# Control.net
KiCad netlist of a schematic drawn in Altium Designer
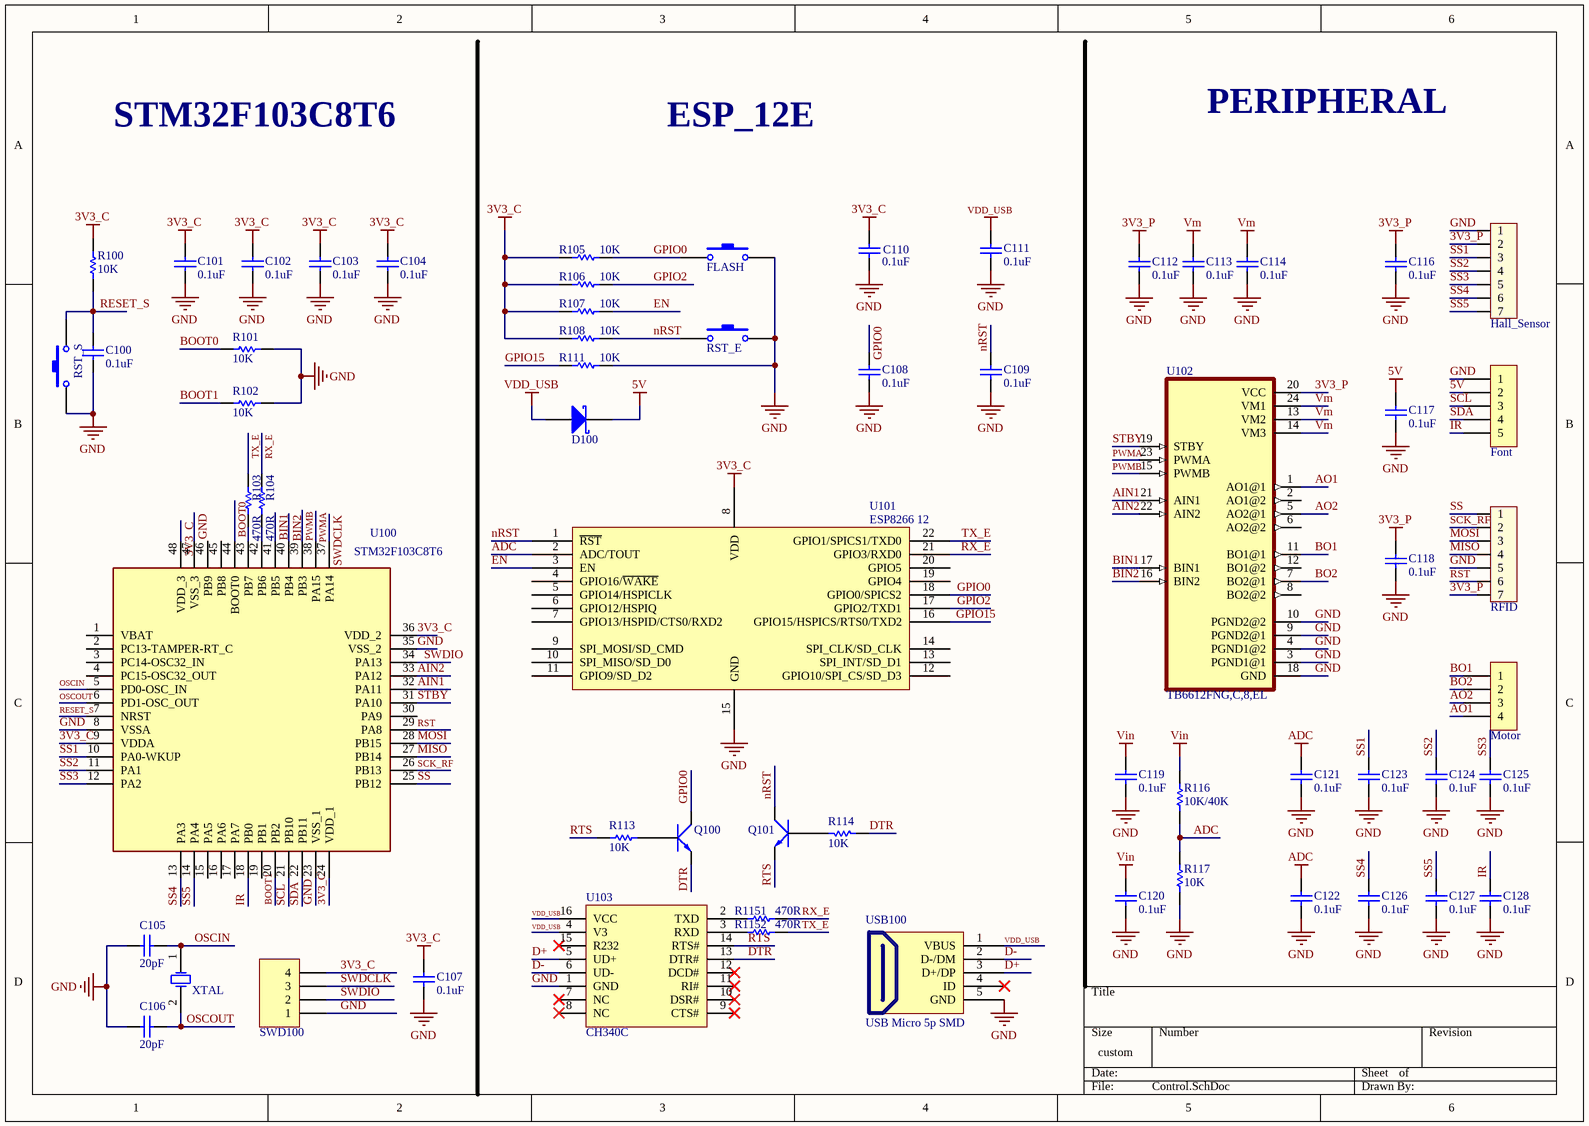
[diagram p0: Control.SchDoc]

(export (version "E")
  (design (tool "Eeschema 10.0.6"))
  (components
    (comp (ref "C100")
      (value "0.1uF")
      (footprint "CAP-SM-0805")
      (description "Capacitor")
      (fields (field (name "Comment") "Cap Non-Pol SMD"))
      (libsource (lib "PIF_Library") (part "Cap Non-Pol SMD"))
    )
    (comp (ref "C101")
      (value "0.1uF")
      (footprint "CAP-SM-0805")
      (description "Capacitor")
      (fields (field (name "Comment") "Cap Non-Pol SMD"))
      (libsource (lib "PIF_Library") (part "Cap Non-Pol SMD"))
    )
    (comp (ref "C102")
      (value "0.1uF")
      (footprint "CAP-SM-0805")
      (description "Capacitor")
      (fields (field (name "Comment") "Cap Non-Pol SMD"))
      (libsource (lib "PIF_Library") (part "Cap Non-Pol SMD"))
    )
    (comp (ref "C103")
      (value "0.1uF")
      (footprint "CAP-SM-0805")
      (description "Capacitor")
      (fields (field (name "Comment") "Cap Non-Pol SMD"))
      (libsource (lib "PIF_Library") (part "Cap Non-Pol SMD"))
    )
    (comp (ref "C104")
      (value "0.1uF")
      (footprint "CAP-SM-0805")
      (description "Capacitor")
      (fields (field (name "Comment") "Cap Non-Pol SMD"))
      (libsource (lib "PIF_Library") (part "Cap Non-Pol SMD"))
    )
    (comp (ref "C105")
      (value "20pF")
      (footprint "CAP-SM-0805")
      (description "Capacitor")
      (fields (field (name "Comment") "Cap Non-Pol SMD"))
      (libsource (lib "PIF_Library") (part "Cap Non-Pol SMD"))
    )
    (comp (ref "C106")
      (value "20pF")
      (footprint "CAP-SM-0805")
      (description "Capacitor")
      (fields (field (name "Comment") "Cap Non-Pol SMD"))
      (libsource (lib "PIF_Library") (part "Cap Non-Pol SMD"))
    )
    (comp (ref "C107")
      (value "0.1uF")
      (footprint "CAP-SM-0805")
      (description "Capacitor")
      (fields (field (name "Comment") "Cap Non-Pol SMD"))
      (libsource (lib "PIF_Library") (part "Cap Non-Pol SMD"))
    )
    (comp (ref "C108")
      (value "0.1uF")
      (footprint "CAP-SM-0805")
      (description "Capacitor")
      (fields (field (name "Comment") "Cap Non-Pol SMD"))
      (libsource (lib "PIF_Library") (part "Cap Non-Pol SMD"))
    )
    (comp (ref "C109")
      (value "0.1uF")
      (footprint "CAP-SM-0805")
      (description "Capacitor")
      (fields (field (name "Comment") "Cap Non-Pol SMD"))
      (libsource (lib "PIF_Library") (part "Cap Non-Pol SMD"))
    )
    (comp (ref "C110")
      (value "0.1uF")
      (footprint "CAP-SM-0805")
      (description "Capacitor")
      (fields (field (name "Comment") "Cap Non-Pol SMD"))
      (libsource (lib "PIF_Library") (part "Cap Non-Pol SMD"))
    )
    (comp (ref "C111")
      (value "0.1uF")
      (footprint "CAP-SM-0805")
      (description "Capacitor")
      (fields (field (name "Comment") "Cap Non-Pol SMD"))
      (libsource (lib "PIF_Library") (part "Cap Non-Pol SMD"))
    )
    (comp (ref "C112")
      (value "0.1uF")
      (footprint "CAP-SM-0805")
      (description "Capacitor")
      (fields (field (name "Comment") "Cap Non-Pol SMD"))
      (libsource (lib "PIF_Library") (part "Cap Non-Pol SMD"))
    )
    (comp (ref "C113")
      (value "0.1uF")
      (footprint "CAP-SM-0805")
      (description "Capacitor")
      (fields (field (name "Comment") "Cap Non-Pol SMD"))
      (libsource (lib "PIF_Library") (part "Cap Non-Pol SMD"))
    )
    (comp (ref "C114")
      (value "0.1uF")
      (footprint "CAP-SM-0805")
      (description "Capacitor")
      (fields (field (name "Comment") "Cap Non-Pol SMD"))
      (libsource (lib "PIF_Library") (part "Cap Non-Pol SMD"))
    )
    (comp (ref "C116")
      (value "0.1uF")
      (footprint "CAP-SM-0805")
      (description "Capacitor")
      (fields (field (name "Comment") "Cap Non-Pol SMD"))
      (libsource (lib "PIF_Library") (part "Cap Non-Pol SMD"))
    )
    (comp (ref "C117")
      (value "0.1uF")
      (footprint "CAP-SM-0805")
      (description "Capacitor")
      (fields (field (name "Comment") "Cap Non-Pol SMD"))
      (libsource (lib "PIF_Library") (part "Cap Non-Pol SMD"))
    )
    (comp (ref "C118")
      (value "0.1uF")
      (footprint "CAP-SM-0805")
      (description "Capacitor")
      (fields (field (name "Comment") "Cap Non-Pol SMD"))
      (libsource (lib "PIF_Library") (part "Cap Non-Pol SMD"))
    )
    (comp (ref "C119")
      (value "0.1uF")
      (footprint "CAP-SM-0805")
      (description "Capacitor")
      (fields (field (name "Comment") "Cap Non-Pol SMD"))
      (libsource (lib "PIF_Library") (part "Cap Non-Pol SMD"))
    )
    (comp (ref "C120")
      (value "0.1uF")
      (footprint "CAP-SM-0805")
      (description "Capacitor")
      (fields (field (name "Comment") "Cap Non-Pol SMD"))
      (libsource (lib "PIF_Library") (part "Cap Non-Pol SMD"))
    )
    (comp (ref "C121")
      (value "0.1uF")
      (footprint "CAP-SM-0805")
      (description "Capacitor")
      (fields (field (name "Comment") "Cap Non-Pol SMD"))
      (libsource (lib "PIF_Library") (part "Cap Non-Pol SMD"))
    )
    (comp (ref "C122")
      (value "0.1uF")
      (footprint "CAP-SM-0805")
      (description "Capacitor")
      (fields (field (name "Comment") "Cap Non-Pol SMD"))
      (libsource (lib "PIF_Library") (part "Cap Non-Pol SMD"))
    )
    (comp (ref "C123")
      (value "0.1uF")
      (footprint "CAP-SM-0805")
      (description "Capacitor")
      (fields (field (name "Comment") "Cap Non-Pol SMD"))
      (libsource (lib "PIF_Library") (part "Cap Non-Pol SMD"))
    )
    (comp (ref "C124")
      (value "0.1uF")
      (footprint "CAP-SM-0805")
      (description "Capacitor")
      (fields (field (name "Comment") "Cap Non-Pol SMD"))
      (libsource (lib "PIF_Library") (part "Cap Non-Pol SMD"))
    )
    (comp (ref "C125")
      (value "0.1uF")
      (footprint "CAP-SM-0805")
      (description "Capacitor")
      (fields (field (name "Comment") "Cap Non-Pol SMD"))
      (libsource (lib "PIF_Library") (part "Cap Non-Pol SMD"))
    )
    (comp (ref "C126")
      (value "0.1uF")
      (footprint "CAP-SM-0805")
      (description "Capacitor")
      (fields (field (name "Comment") "Cap Non-Pol SMD"))
      (libsource (lib "PIF_Library") (part "Cap Non-Pol SMD"))
    )
    (comp (ref "C127")
      (value "0.1uF")
      (footprint "CAP-SM-0805")
      (description "Capacitor")
      (fields (field (name "Comment") "Cap Non-Pol SMD"))
      (libsource (lib "PIF_Library") (part "Cap Non-Pol SMD"))
    )
    (comp (ref "C128")
      (value "0.1uF")
      (footprint "CAP-SM-0805")
      (description "Capacitor")
      (fields (field (name "Comment") "Cap Non-Pol SMD"))
      (libsource (lib "PIF_Library") (part "Cap Non-Pol SMD"))
    )
    (comp (ref "D100")
      (value "D Schottky")
      (footprint "SS34")
      (description "Schottky Diode")
      (fields (field (name "PUBLISHER") "Altium Limited"))
      (libsource (lib "PIF_Library") (part "D Schottky"))
    )
    (comp (ref "FLASH")
      (value "Tact SW - 2Pin")
      (footprint "SW-SMD")
      (description "Switch button 2 pin")
      (libsource (lib "PIF_Library") (part "Tact SW - 2Pin"))
    )
    (comp (ref "H100")
      (value "Hall_Sensor")
      (footprint "Header 7P DC 2.54")
      (description "Cắm")
      (libsource (lib "Altium_Lib_by_KhueNguyenCreator") (part "Header 7P 2.54 Duc Cong"))
    )
    (comp (ref "H101")
      (value "Font")
      (footprint "Header 5P DC 2.54")
      (description "Cắm")
      (libsource (lib "Altium_Lib_by_KhueNguyenCreator") (part "Header 5P 2.54 Duc Cong"))
    )
    (comp (ref "H102")
      (value "RFID")
      (footprint "Header 7P DC 2.54")
      (description "Cắm")
      (libsource (lib "Altium_Lib_by_KhueNguyenCreator") (part "Header 7P 2.54 Duc Cong"))
    )
    (comp (ref "H103")
      (value "Motor")
      (footprint "JP 1x4 DT")
      (description "Cắm")
      (libsource (lib "Altium_Lib_by_KhueNguyenCreator") (part "Header 4P 2.54 Duc Cong"))
    )
    (comp (ref "Q100")
      (value "HF")
      (footprint "SOT23")
      (description "NPN transistor")
      (libsource (lib "Altium_Lib_by_KhueNguyenCreator") (part "C1815 HF SMD"))
    )
    (comp (ref "Q101")
      (value "HF")
      (footprint "SOT23")
      (description "NPN transistor")
      (libsource (lib "Altium_Lib_by_KhueNguyenCreator") (part "C1815 HF SMD"))
    )
    (comp (ref "R100")
      (value "10K")
      (footprint "RES-SM-0805")
      (description "Resistor")
      (fields (field (name "Comment") "RESISTOR SMD"))
      (libsource (lib "PIF_Library") (part "RESISTOR SMD"))
    )
    (comp (ref "R101")
      (value "10K")
      (footprint "RES-SM-0805")
      (description "Resistor")
      (fields (field (name "Comment") "RESISTOR SMD"))
      (libsource (lib "PIF_Library") (part "RESISTOR SMD"))
    )
    (comp (ref "R102")
      (value "10K")
      (footprint "RES-SM-0805")
      (description "Resistor")
      (fields (field (name "Comment") "RESISTOR SMD"))
      (libsource (lib "PIF_Library") (part "RESISTOR SMD"))
    )
    (comp (ref "R103")
      (value "470R")
      (footprint "RES-SM-0805")
      (description "Resistor")
      (fields (field (name "Comment") "RESISTOR SMD"))
      (libsource (lib "PIF_Library") (part "RESISTOR SMD"))
    )
    (comp (ref "R104")
      (value "470R")
      (footprint "RES-SM-0805")
      (description "Resistor")
      (fields (field (name "Comment") "RESISTOR SMD"))
      (libsource (lib "PIF_Library") (part "RESISTOR SMD"))
    )
    (comp (ref "R105")
      (value "10K")
      (footprint "RES-SM-0805")
      (description "Resistor")
      (fields (field (name "Comment") "RESISTOR SMD"))
      (libsource (lib "PIF_Library") (part "RESISTOR SMD"))
    )
    (comp (ref "R106")
      (value "10K")
      (footprint "RES-SM-0805")
      (description "Resistor")
      (fields (field (name "Comment") "RESISTOR SMD"))
      (libsource (lib "PIF_Library") (part "RESISTOR SMD"))
    )
    (comp (ref "R107")
      (value "10K")
      (footprint "RES-SM-0805")
      (description "Resistor")
      (fields (field (name "Comment") "RESISTOR SMD"))
      (libsource (lib "PIF_Library") (part "RESISTOR SMD"))
    )
    (comp (ref "R108")
      (value "10K")
      (footprint "RES-SM-0805")
      (description "Resistor")
      (fields (field (name "Comment") "RESISTOR SMD"))
      (libsource (lib "PIF_Library") (part "RESISTOR SMD"))
    )
    (comp (ref "R111")
      (value "10K")
      (footprint "RES-SM-0805")
      (description "Resistor")
      (fields (field (name "Comment") "RESISTOR SMD"))
      (libsource (lib "PIF_Library") (part "RESISTOR SMD"))
    )
    (comp (ref "R113")
      (value "10K")
      (footprint "RES-SM-0805")
      (description "Resistor")
      (fields (field (name "Comment") "RESISTOR SMD"))
      (libsource (lib "PIF_Library") (part "RESISTOR SMD"))
    )
    (comp (ref "R114")
      (value "10K")
      (footprint "RES-SM-0805")
      (description "Resistor")
      (fields (field (name "Comment") "RESISTOR SMD"))
      (libsource (lib "PIF_Library") (part "RESISTOR SMD"))
    )
    (comp (ref "R116")
      (value "10K/40K")
      (footprint "RES-SM-0805")
      (description "Resistor")
      (fields (field (name "Comment") "RESISTOR SMD"))
      (libsource (lib "PIF_Library") (part "RESISTOR SMD"))
    )
    (comp (ref "R117")
      (value "10K")
      (footprint "RES-SM-0805")
      (description "Resistor")
      (fields (field (name "Comment") "RESISTOR SMD"))
      (libsource (lib "PIF_Library") (part "RESISTOR SMD"))
    )
    (comp (ref "R1151")
      (value "470R")
      (footprint "RES-SM-0805")
      (description "Resistor")
      (fields (field (name "Comment") "RESISTOR SMD"))
      (libsource (lib "PIF_Library") (part "RESISTOR SMD"))
    )
    (comp (ref "R1152")
      (value "470R")
      (footprint "RES-SM-0805")
      (description "Resistor")
      (fields (field (name "Comment") "RESISTOR SMD"))
      (libsource (lib "PIF_Library") (part "RESISTOR SMD"))
    )
    (comp (ref "RST_E")
      (value "Tact SW - 2Pin")
      (footprint "SW-SMD")
      (description "Switch button 2 pin")
      (libsource (lib "PIF_Library") (part "Tact SW - 2Pin"))
    )
    (comp (ref "RST_S")
      (value "Tact SW - 2Pin")
      (footprint "SW-SMD")
      (description "Switch button 2 pin")
      (libsource (lib "PIF_Library") (part "Tact SW - 2Pin"))
    )
    (comp (ref "SWD100")
      (value "Header 4H")
      (footprint "JP4")
      (description "Header, 4-Pin, Right Angle")
      (fields (field (name "PUBLISHER") "Altium Limited"))
      (libsource (lib "PIF_Library") (part "Header 4H"))
    )
    (comp (ref "U100")
      (value "STM32F103C8T6")
      (footprint "LQFP-48_19.6_393_58X11_SMD")
      (description "ARM® Cortex®-M3 STM32F1 Microcontroller IC 32-Bit 72MHz 64KB (64K x 8) FLASH 48-LQFP (7x7)")
      (fields (field (name "MANUFACTURER") "STMicroelectronics"))
      (libsource (lib "Altium_Lib_by_KhueNguyenCreator") (part "IC_STM32F103C8T6"))
    )
    (comp (ref "U101")
      (value "ESP8266 12")
      (footprint "ESP8266 12")
      (description "ESP8266 12 22 Pin")
      (libsource (lib "Altium_Lib_by_KhueNguyenCreator") (part "ESP8266 12"))
    )
    (comp (ref "U102")
      (value "TB6612FNG,C,8,EL")
      (footprint "SOP65P760X160-24N")
      (description "- Motor Driver Power MOSFET Parallel 24-SSOP")
      (fields (field (name "MF") "Toshiba"))
      (libsource (lib "TB6612FNG_C_8_EL") (part "TB6612FNG,C,8,EL"))
    )
    (comp (ref "U103")
      (value "CH340C")
      (footprint "SOIC16_50_284_25X90_SMT")
      (description "USB Bridge, USB to UART USB 2.0 UART Interface")
      (fields (field (name "MANUFACTURER") "Olimex"))
      (libsource (lib "Altium_Lib_by_KhueNguyenCreator") (part "IC_CH340C"))
    )
    (comp (ref "USB100")
      (value "USB Micro 5p SMD")
      (footprint "USB Micro 5p SMD")
      (description "USB Type B")
      (libsource (lib "Altium_Lib_by_KhueNguyenCreator") (part "USB Micro 5p SMD"))
    )
    (comp (ref "XTAL")
      (value "XTAL")
      (footprint "XT2")
      (description "Crystal Oscillator")
      (fields (field (name "PUBLISHER") "Altium Limited"))
      (libsource (lib "PIF_Library") (part "XTAL"))
    )
  )
  (nets
    (net (code "1") (name "/AIN1") (class "Default")
      (node (ref "U100") (pin "32") (pinfunction "PA11_32") (pintype "passive"))
      (node (ref "U102") (pin "21") (pinfunction "AIN1_21") (pintype "input"))
    )
    (net (code "2") (name "/AIN2") (class "Default")
      (node (ref "U100") (pin "33") (pinfunction "PA12_33") (pintype "passive"))
      (node (ref "U102") (pin "22") (pinfunction "AIN2_22") (pintype "input"))
    )
    (net (code "3") (name "/AO1") (class "Default")
      (node (ref "H103") (pin "4") (pinfunction "4_4") (pintype "passive"))
      (node (ref "U102") (pin "1") (pinfunction "AO1@1_1") (pintype "output"))
    )
    (net (code "4") (name "/AO2") (class "Default")
      (node (ref "H103") (pin "3") (pinfunction "3_3") (pintype "passive"))
      (node (ref "U102") (pin "5") (pinfunction "AO2@1_5") (pintype "output"))
    )
    (net (code "5") (name "/BIN1") (class "Default")
      (node (ref "U100") (pin "41") (pinfunction "PB5_41") (pintype "passive"))
      (node (ref "U102") (pin "17") (pinfunction "BIN1_17") (pintype "input"))
    )
    (net (code "6") (name "/BIN2") (class "Default")
      (node (ref "U100") (pin "40") (pinfunction "PB4_40") (pintype "passive"))
      (node (ref "U102") (pin "16") (pinfunction "BIN2_16") (pintype "input"))
    )
    (net (code "7") (name "/BO1") (class "Default")
      (node (ref "H103") (pin "1") (pinfunction "1_1") (pintype "passive"))
      (node (ref "U102") (pin "11") (pinfunction "BO1@1_11") (pintype "output"))
    )
    (net (code "8") (name "/BO2") (class "Default")
      (node (ref "H103") (pin "2") (pinfunction "2_2") (pintype "passive"))
      (node (ref "U102") (pin "7") (pinfunction "BO2@1_7") (pintype "output"))
    )
    (net (code "9") (name "/BOOT0") (class "Default")
      (node (ref "R101") (pin "1") (pinfunction "1_1") (pintype "passive"))
      (node (ref "U100") (pin "44") (pinfunction "BOOT0_44") (pintype "passive"))
    )
    (net (code "10") (name "/BOOT1") (class "Default")
      (node (ref "R102") (pin "2") (pinfunction "2_2") (pintype "passive"))
      (node (ref "U100") (pin "20") (pinfunction "PB2_20") (pintype "passive"))
    )
    (net (code "11") (name "/D+") (class "Default")
      (node (ref "U103") (pin "5") (pinfunction "UD+_5") (pintype "passive"))
      (node (ref "USB100") (pin "3") (pinfunction "D+/DP_3") (pintype "passive"))
    )
    (net (code "12") (name "/D-") (class "Default")
      (node (ref "U103") (pin "6") (pinfunction "UD-_6") (pintype "passive"))
      (node (ref "USB100") (pin "2") (pinfunction "D-/DM_2") (pintype "passive"))
    )
    (net (code "13") (name "/DTR") (class "Default")
      (node (ref "Q100") (pin "2") (pinfunction "E_2") (pintype "passive"))
      (node (ref "R114") (pin "1") (pinfunction "1_1") (pintype "passive"))
      (node (ref "U103") (pin "13") (pinfunction "DTR#_13") (pintype "passive"))
    )
    (net (code "14") (name "/EN") (class "Default")
      (node (ref "R107") (pin "1") (pinfunction "1_1") (pintype "passive"))
      (node (ref "U101") (pin "3") (pinfunction "EN_3") (pintype "passive"))
    )
    (net (code "15") (name "/GPIO0") (class "Default")
      (node (ref "C108") (pin "2") (pinfunction "2_2") (pintype "passive"))
      (node (ref "FLASH") (pin "2") (pinfunction "2_2") (pintype "passive"))
      (node (ref "Q100") (pin "3") (pinfunction "C_3") (pintype "passive"))
      (node (ref "R105") (pin "1") (pinfunction "1_1") (pintype "passive"))
      (node (ref "U101") (pin "18") (pinfunction "GPIO0/SPICS2_18") (pintype "passive"))
    )
    (net (code "16") (name "/GPIO2") (class "Default")
      (node (ref "R106") (pin "1") (pinfunction "1_1") (pintype "passive"))
      (node (ref "U101") (pin "17") (pinfunction "GPIO2/TXD1_17") (pintype "passive"))
    )
    (net (code "17") (name "/GPIO15") (class "Default")
      (node (ref "R111") (pin "2") (pinfunction "2_2") (pintype "passive"))
      (node (ref "U101") (pin "16") (pinfunction "GPIO15/HSPICS/RTS0/TXD2_16") (pintype "passive"))
    )
    (net (code "18") (name "/IR") (class "Default")
      (node (ref "C128") (pin "2") (pinfunction "2_2") (pintype "passive"))
      (node (ref "H101") (pin "5") (pinfunction "5_5") (pintype "passive"))
      (node (ref "U100") (pin "18") (pinfunction "PB0_18") (pintype "passive"))
    )
    (net (code "19") (name "/MISO") (class "Default")
      (node (ref "H102") (pin "4") (pinfunction "4_4") (pintype "passive"))
      (node (ref "U100") (pin "27") (pinfunction "PB14_27") (pintype "passive"))
    )
    (net (code "20") (name "/MOSI") (class "Default")
      (node (ref "H102") (pin "3") (pinfunction "3_3") (pintype "passive"))
      (node (ref "U100") (pin "28") (pinfunction "PB15_28") (pintype "passive"))
    )
    (net (code "21") (name "/OSCIN") (class "Default")
      (node (ref "C105") (pin "2") (pinfunction "2_2") (pintype "passive"))
      (node (ref "U100") (pin "5") (pinfunction "PD0-OSC_IN_5") (pintype "passive"))
      (node (ref "XTAL") (pin "1") (pinfunction "OSC1_1") (pintype "passive"))
    )
    (net (code "22") (name "/OSCOUT") (class "Default")
      (node (ref "C106") (pin "2") (pinfunction "2_2") (pintype "passive"))
      (node (ref "U100") (pin "6") (pinfunction "PD1-OSC_OUT_6") (pintype "passive"))
      (node (ref "XTAL") (pin "2") (pinfunction "OSC2_2") (pintype "passive"))
    )
    (net (code "23") (name "/PWMA") (class "Default")
      (node (ref "U100") (pin "38") (pinfunction "PA15_38") (pintype "passive"))
      (node (ref "U102") (pin "23") (pinfunction "PWMA_23") (pintype "input"))
    )
    (net (code "24") (name "/PWMB") (class "Default")
      (node (ref "U100") (pin "39") (pinfunction "PB3_39") (pintype "passive"))
      (node (ref "U102") (pin "15") (pinfunction "PWMB_15") (pintype "input"))
    )
    (net (code "25") (name "/RESET_S") (class "Default")
      (node (ref "C100") (pin "2") (pinfunction "2_2") (pintype "passive"))
      (node (ref "R100") (pin "1") (pinfunction "1_1") (pintype "passive"))
      (node (ref "RST_S") (pin "2") (pinfunction "2_2") (pintype "passive"))
      (node (ref "U100") (pin "7") (pinfunction "NRST_7") (pintype "passive"))
    )
    (net (code "26") (name "/RST") (class "Default")
      (node (ref "H102") (pin "6") (pinfunction "6_6") (pintype "passive"))
      (node (ref "U100") (pin "29") (pinfunction "PA8_29") (pintype "passive"))
    )
    (net (code "27") (name "/RTS") (class "Default")
      (node (ref "Q101") (pin "2") (pinfunction "E_2") (pintype "passive"))
      (node (ref "R113") (pin "1") (pinfunction "1_1") (pintype "passive"))
      (node (ref "U103") (pin "14") (pinfunction "RTS#_14") (pintype "passive"))
    )
    (net (code "28") (name "/RX_E") (class "Default")
      (node (ref "R104") (pin "2") (pinfunction "2_2") (pintype "passive"))
      (node (ref "R1151") (pin "1") (pinfunction "1_1") (pintype "passive"))
      (node (ref "U101") (pin "21") (pinfunction "GPIO3/RXD0_21") (pintype "passive"))
    )
    (net (code "29") (name "/SCK_RF") (class "Default")
      (node (ref "H102") (pin "2") (pinfunction "2_2") (pintype "passive"))
      (node (ref "U100") (pin "26") (pinfunction "PB13_26") (pintype "passive"))
    )
    (net (code "30") (name "/SCL") (class "Default")
      (node (ref "H101") (pin "3") (pinfunction "3_3") (pintype "passive"))
      (node (ref "U100") (pin "21") (pinfunction "PB10_21") (pintype "passive"))
    )
    (net (code "31") (name "/SDA") (class "Default")
      (node (ref "H101") (pin "4") (pinfunction "4_4") (pintype "passive"))
      (node (ref "U100") (pin "22") (pinfunction "PB11_22") (pintype "passive"))
    )
    (net (code "32") (name "/SS") (class "Default")
      (node (ref "H102") (pin "1") (pinfunction "1_1") (pintype "passive"))
      (node (ref "U100") (pin "25") (pinfunction "PB12_25") (pintype "passive"))
    )
    (net (code "33") (name "/SS1") (class "Default")
      (node (ref "C123") (pin "2") (pinfunction "2_2") (pintype "passive"))
      (node (ref "H100") (pin "3") (pinfunction "3_3") (pintype "passive"))
      (node (ref "U100") (pin "10") (pinfunction "PA0-WKUP_10") (pintype "passive"))
    )
    (net (code "34") (name "/SS2") (class "Default")
      (node (ref "C124") (pin "2") (pinfunction "2_2") (pintype "passive"))
      (node (ref "H100") (pin "4") (pinfunction "4_4") (pintype "passive"))
      (node (ref "U100") (pin "11") (pinfunction "PA1_11") (pintype "passive"))
    )
    (net (code "35") (name "/SS3") (class "Default")
      (node (ref "C125") (pin "2") (pinfunction "2_2") (pintype "passive"))
      (node (ref "H100") (pin "5") (pinfunction "5_5") (pintype "passive"))
      (node (ref "U100") (pin "12") (pinfunction "PA2_12") (pintype "passive"))
    )
    (net (code "36") (name "/SS4") (class "Default")
      (node (ref "C126") (pin "2") (pinfunction "2_2") (pintype "passive"))
      (node (ref "H100") (pin "6") (pinfunction "6_6") (pintype "passive"))
      (node (ref "U100") (pin "13") (pinfunction "PA3_13") (pintype "passive"))
    )
    (net (code "37") (name "/SS5") (class "Default")
      (node (ref "C127") (pin "2") (pinfunction "2_2") (pintype "passive"))
      (node (ref "H100") (pin "7") (pinfunction "7_7") (pintype "passive"))
      (node (ref "U100") (pin "14") (pinfunction "PA4_14") (pintype "passive"))
    )
    (net (code "38") (name "/STBY") (class "Default")
      (node (ref "U100") (pin "31") (pinfunction "PA10_31") (pintype "passive"))
      (node (ref "U102") (pin "19") (pinfunction "STBY_19") (pintype "input"))
    )
    (net (code "39") (name "/SWDCLK") (class "Default")
      (node (ref "SWD100") (pin "3") (pinfunction "3_3") (pintype "passive"))
      (node (ref "U100") (pin "37") (pinfunction "PA14_37") (pintype "passive"))
    )
    (net (code "40") (name "/SWDIO") (class "Default")
      (node (ref "SWD100") (pin "2") (pinfunction "2_2") (pintype "passive"))
      (node (ref "U100") (pin "34") (pinfunction "PA13_34") (pintype "passive"))
    )
    (net (code "41") (name "/TX_E") (class "Default")
      (node (ref "R103") (pin "2") (pinfunction "2_2") (pintype "passive"))
      (node (ref "R1152") (pin "1") (pinfunction "1_1") (pintype "passive"))
      (node (ref "U101") (pin "22") (pinfunction "GPIO1/SPICS1/TXD0_22") (pintype "passive"))
    )
    (net (code "42") (name "/nRST") (class "Default")
      (node (ref "C109") (pin "2") (pinfunction "2_2") (pintype "passive"))
      (node (ref "Q101") (pin "3") (pinfunction "C_3") (pintype "passive"))
      (node (ref "R108") (pin "1") (pinfunction "1_1") (pintype "passive"))
      (node (ref "RST_E") (pin "2") (pinfunction "2_2") (pintype "passive"))
      (node (ref "U101") (pin "1") (pinfunction "~{RST}_1") (pintype "passive"))
    )
    (net (code "43") (name "3V3_C") (class "Default")
      (node (ref "C101") (pin "2") (pinfunction "2_2") (pintype "passive"))
      (node (ref "C102") (pin "2") (pinfunction "2_2") (pintype "passive"))
      (node (ref "C103") (pin "2") (pinfunction "2_2") (pintype "passive"))
      (node (ref "C104") (pin "2") (pinfunction "2_2") (pintype "passive"))
      (node (ref "C107") (pin "2") (pinfunction "2_2") (pintype "passive"))
      (node (ref "C110") (pin "2") (pinfunction "2_2") (pintype "passive"))
      (node (ref "R100") (pin "2") (pinfunction "2_2") (pintype "passive"))
      (node (ref "R105") (pin "2") (pinfunction "2_2") (pintype "passive"))
      (node (ref "R106") (pin "2") (pinfunction "2_2") (pintype "passive"))
      (node (ref "R107") (pin "2") (pinfunction "2_2") (pintype "passive"))
      (node (ref "R108") (pin "2") (pinfunction "2_2") (pintype "passive"))
      (node (ref "SWD100") (pin "4") (pinfunction "4_4") (pintype "passive"))
      (node (ref "U100") (pin "24") (pinfunction "VDD_1_24") (pintype "passive"))
      (node (ref "U100") (pin "36") (pinfunction "VDD_2_36") (pintype "passive"))
      (node (ref "U100") (pin "48") (pinfunction "VDD_3_48") (pintype "passive"))
      (node (ref "U100") (pin "9") (pinfunction "VDDA_9") (pintype "passive"))
      (node (ref "U101") (pin "8") (pinfunction "VDD_8") (pintype "passive"))
    )
    (net (code "44") (name "3V3_P") (class "Default")
      (node (ref "C112") (pin "2") (pinfunction "2_2") (pintype "passive"))
      (node (ref "C116") (pin "2") (pinfunction "2_2") (pintype "passive"))
      (node (ref "C118") (pin "2") (pinfunction "2_2") (pintype "passive"))
      (node (ref "H100") (pin "2") (pinfunction "2_2") (pintype "passive"))
      (node (ref "H102") (pin "7") (pinfunction "7_7") (pintype "passive"))
      (node (ref "U102") (pin "20") (pinfunction "VCC_20") (pintype "power_in"))
    )
    (net (code "45") (name "5V") (class "Default")
      (node (ref "C117") (pin "2") (pinfunction "2_2") (pintype "passive"))
      (node (ref "D100") (pin "2") (pinfunction "K_2") (pintype "passive"))
      (node (ref "H101") (pin "2") (pinfunction "2_2") (pintype "passive"))
    )
    (net (code "46") (name "ADC") (class "Default")
      (node (ref "C121") (pin "2") (pinfunction "2_2") (pintype "passive"))
      (node (ref "C122") (pin "2") (pinfunction "2_2") (pintype "passive"))
      (node (ref "R116") (pin "1") (pinfunction "1_1") (pintype "passive"))
      (node (ref "R117") (pin "2") (pinfunction "2_2") (pintype "passive"))
      (node (ref "U101") (pin "2") (pinfunction "ADC/TOUT_2") (pintype "passive"))
    )
    (net (code "47") (name "GND") (class "Default")
      (node (ref "C100") (pin "1") (pinfunction "1_1") (pintype "passive"))
      (node (ref "C101") (pin "1") (pinfunction "1_1") (pintype "passive"))
      (node (ref "C102") (pin "1") (pinfunction "1_1") (pintype "passive"))
      (node (ref "C103") (pin "1") (pinfunction "1_1") (pintype "passive"))
      (node (ref "C104") (pin "1") (pinfunction "1_1") (pintype "passive"))
      (node (ref "C105") (pin "1") (pinfunction "1_1") (pintype "passive"))
      (node (ref "C106") (pin "1") (pinfunction "1_1") (pintype "passive"))
      (node (ref "C107") (pin "1") (pinfunction "1_1") (pintype "passive"))
      (node (ref "C108") (pin "1") (pinfunction "1_1") (pintype "passive"))
      (node (ref "C109") (pin "1") (pinfunction "1_1") (pintype "passive"))
      (node (ref "C110") (pin "1") (pinfunction "1_1") (pintype "passive"))
      (node (ref "C111") (pin "1") (pinfunction "1_1") (pintype "passive"))
      (node (ref "C112") (pin "1") (pinfunction "1_1") (pintype "passive"))
      (node (ref "C113") (pin "1") (pinfunction "1_1") (pintype "passive"))
      (node (ref "C114") (pin "1") (pinfunction "1_1") (pintype "passive"))
      (node (ref "C116") (pin "1") (pinfunction "1_1") (pintype "passive"))
      (node (ref "C117") (pin "1") (pinfunction "1_1") (pintype "passive"))
      (node (ref "C118") (pin "1") (pinfunction "1_1") (pintype "passive"))
      (node (ref "C119") (pin "1") (pinfunction "1_1") (pintype "passive"))
      (node (ref "C120") (pin "1") (pinfunction "1_1") (pintype "passive"))
      (node (ref "C121") (pin "1") (pinfunction "1_1") (pintype "passive"))
      (node (ref "C122") (pin "1") (pinfunction "1_1") (pintype "passive"))
      (node (ref "C123") (pin "1") (pinfunction "1_1") (pintype "passive"))
      (node (ref "C124") (pin "1") (pinfunction "1_1") (pintype "passive"))
      (node (ref "C125") (pin "1") (pinfunction "1_1") (pintype "passive"))
      (node (ref "C126") (pin "1") (pinfunction "1_1") (pintype "passive"))
      (node (ref "C127") (pin "1") (pinfunction "1_1") (pintype "passive"))
      (node (ref "C128") (pin "1") (pinfunction "1_1") (pintype "passive"))
      (node (ref "FLASH") (pin "1") (pinfunction "1_1") (pintype "passive"))
      (node (ref "H100") (pin "1") (pinfunction "1_1") (pintype "passive"))
      (node (ref "H101") (pin "1") (pinfunction "1_1") (pintype "passive"))
      (node (ref "H102") (pin "5") (pinfunction "5_5") (pintype "passive"))
      (node (ref "R101") (pin "2") (pinfunction "2_2") (pintype "passive"))
      (node (ref "R102") (pin "1") (pinfunction "1_1") (pintype "passive"))
      (node (ref "R111") (pin "1") (pinfunction "1_1") (pintype "passive"))
      (node (ref "R117") (pin "1") (pinfunction "1_1") (pintype "passive"))
      (node (ref "RST_E") (pin "1") (pinfunction "1_1") (pintype "passive"))
      (node (ref "RST_S") (pin "1") (pinfunction "1_1") (pintype "passive"))
      (node (ref "SWD100") (pin "1") (pinfunction "1_1") (pintype "passive"))
      (node (ref "U100") (pin "23") (pinfunction "VSS_1_23") (pintype "passive"))
      (node (ref "U100") (pin "35") (pinfunction "VSS_2_35") (pintype "passive"))
      (node (ref "U100") (pin "47") (pinfunction "VSS_3_47") (pintype "passive"))
      (node (ref "U100") (pin "8") (pinfunction "VSSA_8") (pintype "passive"))
      (node (ref "U101") (pin "15") (pinfunction "GND_15") (pintype "passive"))
      (node (ref "U102") (pin "10") (pinfunction "PGND2@2_10") (pintype "passive"))
      (node (ref "U102") (pin "18") (pinfunction "GND_18") (pintype "passive"))
      (node (ref "U102") (pin "3") (pinfunction "PGND1@1_3") (pintype "passive"))
      (node (ref "U102") (pin "4") (pinfunction "PGND1@2_4") (pintype "passive"))
      (node (ref "U102") (pin "9") (pinfunction "PGND2@1_9") (pintype "passive"))
      (node (ref "U103") (pin "1") (pinfunction "GND_1") (pintype "passive"))
      (node (ref "USB100") (pin "5") (pinfunction "GND_5") (pintype "passive"))
    )
    (net (code "48") (name "Net-(Q100-B)") (class "Default")
      (node (ref "Q100") (pin "1") (pinfunction "B_1") (pintype "passive"))
      (node (ref "R113") (pin "2") (pinfunction "2_2") (pintype "passive"))
    )
    (net (code "49") (name "Net-(Q101-B)") (class "Default")
      (node (ref "Q101") (pin "1") (pinfunction "B_1") (pintype "passive"))
      (node (ref "R114") (pin "2") (pinfunction "2_2") (pintype "passive"))
    )
    (net (code "50") (name "Net-(U100-PB6)") (class "Default")
      (node (ref "R104") (pin "1") (pinfunction "1_1") (pintype "passive"))
      (node (ref "U100") (pin "42") (pinfunction "PB6_42") (pintype "passive"))
    )
    (net (code "51") (name "Net-(U100-PB7)") (class "Default")
      (node (ref "R103") (pin "1") (pinfunction "1_1") (pintype "passive"))
      (node (ref "U100") (pin "43") (pinfunction "PB7_43") (pintype "passive"))
    )
    (net (code "52") (name "Net-(U103-RXD)") (class "Default")
      (node (ref "R1152") (pin "2") (pinfunction "2_2") (pintype "passive"))
      (node (ref "U103") (pin "3") (pinfunction "RXD_3") (pintype "passive"))
    )
    (net (code "53") (name "Net-(U103-TXD)") (class "Default")
      (node (ref "R1151") (pin "2") (pinfunction "2_2") (pintype "passive"))
      (node (ref "U103") (pin "2") (pinfunction "TXD_2") (pintype "passive"))
    )
    (net (code "54") (name "VDD_USB") (class "Default")
      (node (ref "C111") (pin "2") (pinfunction "2_2") (pintype "passive"))
      (node (ref "D100") (pin "1") (pinfunction "A_1") (pintype "passive"))
      (node (ref "U103") (pin "16") (pinfunction "VCC_16") (pintype "passive"))
      (node (ref "U103") (pin "4") (pinfunction "V3_4") (pintype "passive"))
      (node (ref "USB100") (pin "1") (pinfunction "VBUS_1") (pintype "passive"))
    )
    (net (code "55") (name "Vin") (class "Default")
      (node (ref "C119") (pin "2") (pinfunction "2_2") (pintype "passive"))
      (node (ref "C120") (pin "2") (pinfunction "2_2") (pintype "passive"))
      (node (ref "R116") (pin "2") (pinfunction "2_2") (pintype "passive"))
    )
    (net (code "56") (name "Vm") (class "Default")
      (node (ref "C113") (pin "2") (pinfunction "2_2") (pintype "passive"))
      (node (ref "C114") (pin "2") (pinfunction "2_2") (pintype "passive"))
      (node (ref "U102") (pin "13") (pinfunction "VM2_13") (pintype "power_in"))
      (node (ref "U102") (pin "14") (pinfunction "VM3_14") (pintype "power_in"))
      (node (ref "U102") (pin "24") (pinfunction "VM1_24") (pintype "power_in"))
    )
    (net (code "57") (name "unconnected-(U100-PA5-Pad15)") (class "Default")
      (node (ref "U100") (pin "15") (pinfunction "PA5_15") (pintype "passive"))
    )
    (net (code "58") (name "unconnected-(U100-PA6-Pad16)") (class "Default")
      (node (ref "U100") (pin "16") (pinfunction "PA6_16") (pintype "passive"))
    )
    (net (code "59") (name "unconnected-(U100-PA7-Pad17)") (class "Default")
      (node (ref "U100") (pin "17") (pinfunction "PA7_17") (pintype "passive"))
    )
    (net (code "60") (name "unconnected-(U100-PA9-Pad30)") (class "Default")
      (node (ref "U100") (pin "30") (pinfunction "PA9_30") (pintype "passive"))
    )
    (net (code "61") (name "unconnected-(U100-PB1-Pad19)") (class "Default")
      (node (ref "U100") (pin "19") (pinfunction "PB1_19") (pintype "passive"))
    )
    (net (code "62") (name "unconnected-(U100-PB8-Pad45)") (class "Default")
      (node (ref "U100") (pin "45") (pinfunction "PB8_45") (pintype "passive"))
    )
    (net (code "63") (name "unconnected-(U100-PB9-Pad46)") (class "Default")
      (node (ref "U100") (pin "46") (pinfunction "PB9_46") (pintype "passive"))
    )
    (net (code "64") (name "unconnected-(U100-PC13-TAMPER-RT_C-Pad2)") (class "Default")
      (node (ref "U100") (pin "2") (pinfunction "PC13-TAMPER-RT_C_2") (pintype "passive"))
    )
    (net (code "65") (name "unconnected-(U100-PC14-OSC32_IN-Pad3)") (class "Default")
      (node (ref "U100") (pin "3") (pinfunction "PC14-OSC32_IN_3") (pintype "passive"))
    )
    (net (code "66") (name "unconnected-(U100-PC15-OSC32_OUT-Pad4)") (class "Default")
      (node (ref "U100") (pin "4") (pinfunction "PC15-OSC32_OUT_4") (pintype "passive"))
    )
    (net (code "67") (name "unconnected-(U100-VBAT-Pad1)") (class "Default")
      (node (ref "U100") (pin "1") (pinfunction "VBAT_1") (pintype "passive"))
    )
    (net (code "68") (name "unconnected-(U101-GPIO4-Pad19)") (class "Default")
      (node (ref "U101") (pin "19") (pinfunction "GPIO4_19") (pintype "passive"))
    )
    (net (code "69") (name "unconnected-(U101-GPIO5-Pad20)") (class "Default")
      (node (ref "U101") (pin "20") (pinfunction "GPIO5_20") (pintype "passive"))
    )
    (net (code "70") (name "unconnected-(U101-GPIO9{slash}SD_D2-Pad11)") (class "Default")
      (node (ref "U101") (pin "11") (pinfunction "GPIO9/SD_D2_11") (pintype "passive"))
    )
    (net (code "71") (name "unconnected-(U101-GPIO10{slash}SPI_CS{slash}SD_D3-Pad12)") (class "Default")
      (node (ref "U101") (pin "12") (pinfunction "GPIO10/SPI_CS/SD_D3_12") (pintype "passive"))
    )
    (net (code "72") (name "unconnected-(U101-GPIO12{slash}HSPIQ-Pad6)") (class "Default")
      (node (ref "U101") (pin "6") (pinfunction "GPIO12/HSPIQ_6") (pintype "passive"))
    )
    (net (code "73") (name "unconnected-(U101-GPIO13{slash}HSPID{slash}CTS0{slash}RXD2-Pad7)") (class "Default")
      (node (ref "U101") (pin "7") (pinfunction "GPIO13/HSPID/CTS0/RXD2_7") (pintype "passive"))
    )
    (net (code "74") (name "unconnected-(U101-GPIO14{slash}HSPICLK-Pad5)") (class "Default")
      (node (ref "U101") (pin "5") (pinfunction "GPIO14/HSPICLK_5") (pintype "passive"))
    )
    (net (code "75") (name "unconnected-(U101-GPIO16{slash}~{WAKE}-Pad4)") (class "Default")
      (node (ref "U101") (pin "4") (pinfunction "GPIO16/~{WAKE}_4") (pintype "passive"))
    )
    (net (code "76") (name "unconnected-(U101-SPI_CLK{slash}SD_CLK-Pad14)") (class "Default")
      (node (ref "U101") (pin "14") (pinfunction "SPI_CLK/SD_CLK_14") (pintype "passive"))
    )
    (net (code "77") (name "unconnected-(U101-SPI_INT{slash}SD_D1-Pad13)") (class "Default")
      (node (ref "U101") (pin "13") (pinfunction "SPI_INT/SD_D1_13") (pintype "passive"))
    )
    (net (code "78") (name "unconnected-(U101-SPI_MISO{slash}SD_D0-Pad10)") (class "Default")
      (node (ref "U101") (pin "10") (pinfunction "SPI_MISO/SD_D0_10") (pintype "passive"))
    )
    (net (code "79") (name "unconnected-(U101-SPI_MOSI{slash}SD_CMD-Pad9)") (class "Default")
      (node (ref "U101") (pin "9") (pinfunction "SPI_MOSI/SD_CMD_9") (pintype "passive"))
    )
    (net (code "80") (name "unconnected-(U102-AO1@2-Pad2)") (class "Default")
      (node (ref "U102") (pin "2") (pinfunction "AO1@2_2") (pintype "output"))
    )
    (net (code "81") (name "unconnected-(U102-AO2@2-Pad6)") (class "Default")
      (node (ref "U102") (pin "6") (pinfunction "AO2@2_6") (pintype "output"))
    )
    (net (code "82") (name "unconnected-(U102-BO1@2-Pad12)") (class "Default")
      (node (ref "U102") (pin "12") (pinfunction "BO1@2_12") (pintype "output"))
    )
    (net (code "83") (name "unconnected-(U102-BO2@2-Pad8)") (class "Default")
      (node (ref "U102") (pin "8") (pinfunction "BO2@2_8") (pintype "output"))
    )
    (net (code "84") (name "unconnected-(U103-CTS#-Pad9)") (class "Default")
      (node (ref "U103") (pin "9") (pinfunction "CTS#_9") (pintype "passive+no_connect"))
    )
    (net (code "85") (name "unconnected-(U103-DCD#-Pad12)") (class "Default")
      (node (ref "U103") (pin "12") (pinfunction "DCD#_12") (pintype "passive+no_connect"))
    )
    (net (code "86") (name "unconnected-(U103-DSR#-Pad10)") (class "Default")
      (node (ref "U103") (pin "10") (pinfunction "DSR#_10") (pintype "passive+no_connect"))
    )
    (net (code "87") (name "unconnected-(U103-NC-Pad7)") (class "Default")
      (node (ref "U103") (pin "7") (pinfunction "NC_7") (pintype "passive+no_connect"))
    )
    (net (code "88") (name "unconnected-(U103-NC-Pad8)") (class "Default")
      (node (ref "U103") (pin "8") (pinfunction "NC_8") (pintype "passive+no_connect"))
    )
    (net (code "89") (name "unconnected-(U103-R232-Pad15)") (class "Default")
      (node (ref "U103") (pin "15") (pinfunction "R232_15") (pintype "passive+no_connect"))
    )
    (net (code "90") (name "unconnected-(U103-RI#-Pad11)") (class "Default")
      (node (ref "U103") (pin "11") (pinfunction "RI#_11") (pintype "passive+no_connect"))
    )
    (net (code "91") (name "unconnected-(USB100-ID-Pad4)") (class "Default")
      (node (ref "USB100") (pin "4") (pinfunction "ID_4") (pintype "passive+no_connect"))
    )
  )
)
